# BlockController.net
KiCad netlist of a schematic drawn in EAGLE
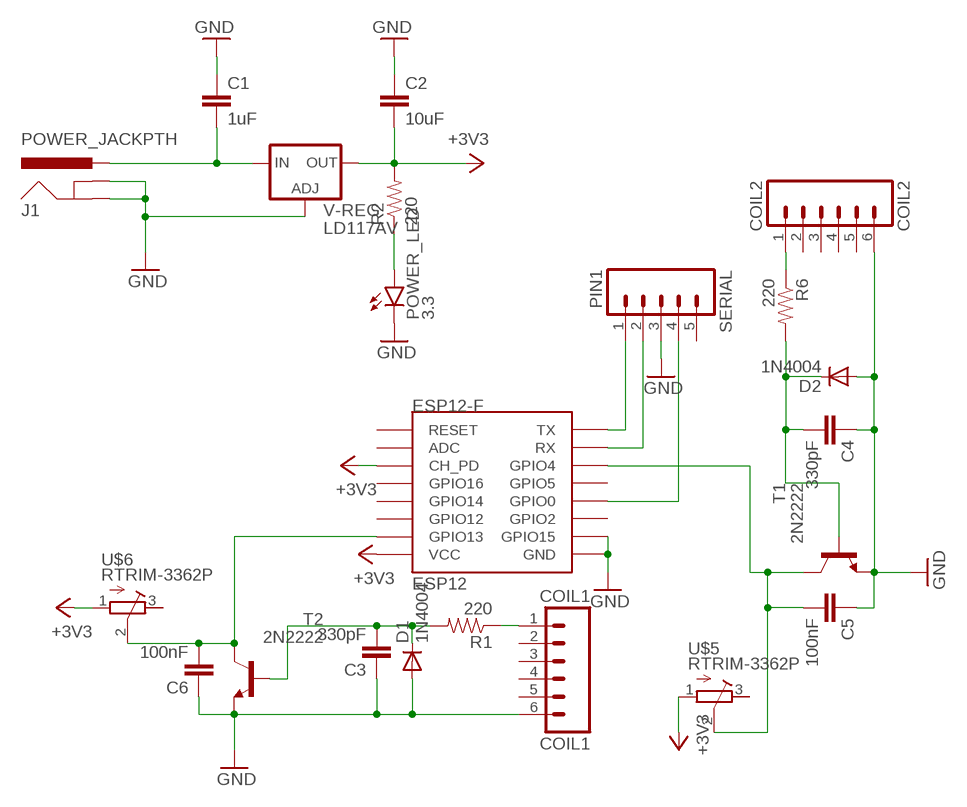
[diagram p0: schematic, sheet 1]

(export (version "E")
  (design (tool "Eeschema 10.0.6"))
  (components
    (comp (ref "C1")
      (value "1uF")
      (footprint "eagle-import:CAP-PTH-SMALL")
      (libsource (lib "eagle-import") (part "CAPPTH"))
    )
    (comp (ref "C2")
      (value "10uF")
      (footprint "eagle-import:CAP-PTH-SMALL")
      (libsource (lib "eagle-import") (part "CAPPTH"))
    )
    (comp (ref "C3")
      (value "330pF")
      (footprint "eagle-import:CAP-PTH-SMALL")
      (libsource (lib "eagle-import") (part "CAPPTH"))
    )
    (comp (ref "C4")
      (value "330pF")
      (footprint "eagle-import:CAP-PTH-SMALL")
      (libsource (lib "eagle-import") (part "CAPPTH"))
    )
    (comp (ref "C5")
      (value "100nF")
      (footprint "eagle-import:CAP-PTH-SMALL")
      (libsource (lib "eagle-import") (part "CAPPTH"))
    )
    (comp (ref "C6")
      (value "100nF")
      (footprint "eagle-import:CAP-PTH-SMALL")
      (libsource (lib "eagle-import") (part "CAPPTH"))
    )
    (comp (ref "COIL1")
      (value "COIL1")
      (footprint "eagle-import:06P")
      (libsource (lib "eagle-import") (part "M06"))
    )
    (comp (ref "COIL2")
      (value "COIL2")
      (footprint "eagle-import:06P")
      (libsource (lib "eagle-import") (part "M06"))
    )
    (comp (ref "D1")
      (value "1N4004")
      (footprint "eagle-import:DO41-10")
      (libsource (lib "eagle-import") (part "1N4004"))
    )
    (comp (ref "D2")
      (value "1N4004")
      (footprint "eagle-import:DO41-10")
      (libsource (lib "eagle-import") (part "1N4004"))
    )
    (comp (ref "ESP12-F")
      (value "ESP12")
      (footprint "eagle-import:ESP12")
      (libsource (lib "eagle-import") (part "ESP12"))
    )
    (comp (ref "J1")
      (value "POWER_JACKPTH")
      (footprint "eagle-import:POWER_JACK_PTH")
      (libsource (lib "eagle-import") (part "POWER_JACKPTH"))
    )
    (comp (ref "POWER_LED")
      (value "3.3")
      (footprint "eagle-import:LED5MM")
      (libsource (lib "eagle-import") (part "LED5MM"))
    )
    (comp (ref "R1")
      (value "220")
      (footprint "eagle-import:AXIAL-0.4")
      (libsource (lib "eagle-import") (part "RESISTORPTH-1/4W"))
    )
    (comp (ref "R2")
      (value "220")
      (footprint "eagle-import:AXIAL-0.4")
      (libsource (lib "eagle-import") (part "RESISTORPTH-1/4W"))
    )
    (comp (ref "R6")
      (value "220")
      (footprint "eagle-import:AXIAL-0.4")
      (libsource (lib "eagle-import") (part "RESISTORPTH-1/4W"))
    )
    (comp (ref "SERIAL")
      (value "PIN1")
      (footprint "eagle-import:05P")
      (libsource (lib "eagle-import") (part "M05"))
    )
    (comp (ref "T1")
      (value "2N2222")
      (footprint "eagle-import:TO18")
      (libsource (lib "eagle-import") (part "2N2222"))
    )
    (comp (ref "T2")
      (value "2N2222")
      (footprint "eagle-import:TO18")
      (libsource (lib "eagle-import") (part "2N2222"))
    )
    (comp (ref "U$5")
      (value "RTRIM-3362P")
      (footprint "eagle-import:RTRIM3362P")
      (libsource (lib "eagle-import") (part "RTRIM-3362P"))
    )
    (comp (ref "U$6")
      (value "RTRIM-3362P")
      (footprint "eagle-import:RTRIM3362P")
      (libsource (lib "eagle-import") (part "RTRIM-3362P"))
    )
    (comp (ref "V-REG")
      (value "LD117AV")
      (footprint "eagle-import:TO220L1")
      (libsource (lib "eagle-import") (part "LD117A?V"))
    )
  )
  (nets
    (net (code "1") (name "+3V3") (class "Default")
      (node (ref "C2") (pin "2") (pinfunction "2_2") (pintype "passive"))
      (node (ref "ESP12-F") (pin "CH_PD") (pinfunction "CH_PD_CH_PD") (pintype "bidirectional"))
      (node (ref "ESP12-F") (pin "VCC") (pinfunction "VCC_VCC") (pintype "bidirectional"))
      (node (ref "R2") (pin "P$2") (pinfunction "2_P$2") (pintype "passive"))
      (node (ref "U$5") (pin "1") (pinfunction "1_1") (pintype "passive"))
      (node (ref "U$6") (pin "1") (pinfunction "1_1") (pintype "passive"))
      (node (ref "V-REG") (pin "2") (pinfunction "OUT_2") (pintype "passive"))
    )
    (net (code "2") (name "GND") (class "Default")
      (node (ref "C1") (pin "1") (pinfunction "1_1") (pintype "passive"))
      (node (ref "C2") (pin "1") (pinfunction "1_1") (pintype "passive"))
      (node (ref "C3") (pin "1") (pinfunction "1_1") (pintype "passive"))
      (node (ref "C4") (pin "1") (pinfunction "1_1") (pintype "passive"))
      (node (ref "C5") (pin "1") (pinfunction "1_1") (pintype "passive"))
      (node (ref "C6") (pin "1") (pinfunction "1_1") (pintype "passive"))
      (node (ref "COIL1") (pin "6") (pinfunction "6_6") (pintype "passive"))
      (node (ref "COIL2") (pin "6") (pinfunction "6_6") (pintype "passive"))
      (node (ref "D1") (pin "A") (pinfunction "A_A") (pintype "passive"))
      (node (ref "D2") (pin "A") (pinfunction "A_A") (pintype "passive"))
      (node (ref "ESP12-F") (pin "GND") (pinfunction "GND_GND") (pintype "bidirectional"))
      (node (ref "ESP12-F") (pin "GPIO15") (pinfunction "GPIO15_GPIO15") (pintype "bidirectional"))
      (node (ref "J1") (pin "GND") (pinfunction "GND_GND") (pintype "bidirectional"))
      (node (ref "J1") (pin "GNDBREAK") (pinfunction "GNDBREAK_GNDBREAK") (pintype "bidirectional"))
      (node (ref "POWER_LED") (pin "K") (pinfunction "C_K") (pintype "passive"))
      (node (ref "SERIAL") (pin "3") (pinfunction "3_3") (pintype "passive"))
      (node (ref "T1") (pin "1") (pinfunction "E_1") (pintype "passive"))
      (node (ref "T2") (pin "1") (pinfunction "E_1") (pintype "passive"))
      (node (ref "V-REG") (pin "1") (pinfunction "ADJ_1") (pintype "input"))
    )
    (net (code "3") (name "Net-(ESP12-F-PadGPIO0)") (class "Default")
      (node (ref "ESP12-F") (pin "GPIO0") (pinfunction "GPIO0_GPIO0") (pintype "bidirectional"))
      (node (ref "SERIAL") (pin "4") (pinfunction "4_4") (pintype "passive"))
    )
    (net (code "4") (name "Net-(ESP12-F-PadRX)") (class "Default")
      (node (ref "ESP12-F") (pin "RX") (pinfunction "RX_RX") (pintype "bidirectional"))
      (node (ref "SERIAL") (pin "2") (pinfunction "2_2") (pintype "passive"))
    )
    (net (code "5") (name "Net-(ESP12-F-PadTX)") (class "Default")
      (node (ref "ESP12-F") (pin "TX") (pinfunction "TX_TX") (pintype "bidirectional"))
      (node (ref "SERIAL") (pin "1") (pinfunction "1_1") (pintype "passive"))
    )
    (net (code "6") (name "Net-(R1-1)") (class "Default")
      (node (ref "COIL1") (pin "1") (pinfunction "1_1") (pintype "passive"))
      (node (ref "R1") (pin "P$1") (pinfunction "1_P$1") (pintype "passive"))
    )
    (net (code "7") (name "Net-(R1-2)") (class "Default")
      (node (ref "C3") (pin "2") (pinfunction "2_2") (pintype "passive"))
      (node (ref "D1") (pin "C") (pinfunction "C_C") (pintype "passive"))
      (node (ref "R1") (pin "P$2") (pinfunction "2_P$2") (pintype "passive"))
      (node (ref "T2") (pin "2") (pinfunction "B_2") (pintype "passive"))
    )
    (net (code "8") (name "Net-(R2-1)") (class "Default")
      (node (ref "POWER_LED") (pin "A") (pinfunction "A_A") (pintype "passive"))
      (node (ref "R2") (pin "P$1") (pinfunction "1_P$1") (pintype "passive"))
    )
    (net (code "9") (name "Net-(R6-1)") (class "Default")
      (node (ref "COIL2") (pin "1") (pinfunction "1_1") (pintype "passive"))
      (node (ref "R6") (pin "P$1") (pinfunction "1_P$1") (pintype "passive"))
    )
    (net (code "10") (name "Net-(R6-2)") (class "Default")
      (node (ref "C4") (pin "2") (pinfunction "2_2") (pintype "passive"))
      (node (ref "D2") (pin "C") (pinfunction "C_C") (pintype "passive"))
      (node (ref "R6") (pin "P$2") (pinfunction "2_P$2") (pintype "passive"))
      (node (ref "T1") (pin "2") (pinfunction "B_2") (pintype "passive"))
    )
    (net (code "11") (name "Net-(T1-C)") (class "Default")
      (node (ref "C5") (pin "2") (pinfunction "2_2") (pintype "passive"))
      (node (ref "ESP12-F") (pin "GPIO4") (pinfunction "GPIO4_GPIO4") (pintype "bidirectional"))
      (node (ref "T1") (pin "3") (pinfunction "C_3") (pintype "passive"))
      (node (ref "U$5") (pin "2") (pinfunction "2_2") (pintype "passive"))
    )
    (net (code "12") (name "Net-(T2-C)") (class "Default")
      (node (ref "C6") (pin "2") (pinfunction "2_2") (pintype "passive"))
      (node (ref "ESP12-F") (pin "GPIO13") (pinfunction "GPIO13_GPIO13") (pintype "bidirectional"))
      (node (ref "T2") (pin "3") (pinfunction "C_3") (pintype "passive"))
      (node (ref "U$6") (pin "2") (pinfunction "2_2") (pintype "passive"))
    )
    (net (code "13") (name "Net-(V-REG-IN)") (class "Default")
      (node (ref "C1") (pin "2") (pinfunction "2_2") (pintype "passive"))
      (node (ref "J1") (pin "PWR") (pinfunction "PWR_PWR") (pintype "bidirectional"))
      (node (ref "V-REG") (pin "3") (pinfunction "IN_3") (pintype "input"))
    )
    (net (code "14") (name "unconnected-(COIL1-Pad2)") (class "Default")
      (node (ref "COIL1") (pin "2") (pinfunction "2_2") (pintype "passive"))
    )
    (net (code "15") (name "unconnected-(COIL1-Pad3)") (class "Default")
      (node (ref "COIL1") (pin "3") (pinfunction "3_3") (pintype "passive"))
    )
    (net (code "16") (name "unconnected-(COIL1-Pad4)") (class "Default")
      (node (ref "COIL1") (pin "4") (pinfunction "4_4") (pintype "passive"))
    )
    (net (code "17") (name "unconnected-(COIL1-Pad5)") (class "Default")
      (node (ref "COIL1") (pin "5") (pinfunction "5_5") (pintype "passive"))
    )
    (net (code "18") (name "unconnected-(COIL2-Pad2)") (class "Default")
      (node (ref "COIL2") (pin "2") (pinfunction "2_2") (pintype "passive"))
    )
    (net (code "19") (name "unconnected-(COIL2-Pad3)") (class "Default")
      (node (ref "COIL2") (pin "3") (pinfunction "3_3") (pintype "passive"))
    )
    (net (code "20") (name "unconnected-(COIL2-Pad4)") (class "Default")
      (node (ref "COIL2") (pin "4") (pinfunction "4_4") (pintype "passive"))
    )
    (net (code "21") (name "unconnected-(COIL2-Pad5)") (class "Default")
      (node (ref "COIL2") (pin "5") (pinfunction "5_5") (pintype "passive"))
    )
    (net (code "22") (name "unconnected-(ESP12-F-PadADC)") (class "Default")
      (node (ref "ESP12-F") (pin "ADC") (pinfunction "ADC_ADC") (pintype "bidirectional"))
    )
    (net (code "23") (name "unconnected-(ESP12-F-PadGPIO2)") (class "Default")
      (node (ref "ESP12-F") (pin "GPIO2") (pinfunction "GPIO2_GPIO2") (pintype "bidirectional"))
    )
    (net (code "24") (name "unconnected-(ESP12-F-PadGPIO5)") (class "Default")
      (node (ref "ESP12-F") (pin "GPIO5") (pinfunction "GPIO5_GPIO5") (pintype "bidirectional"))
    )
    (net (code "25") (name "unconnected-(ESP12-F-PadGPIO12)") (class "Default")
      (node (ref "ESP12-F") (pin "GPIO12") (pinfunction "GPIO12_GPIO12") (pintype "bidirectional"))
    )
    (net (code "26") (name "unconnected-(ESP12-F-PadGPIO14)") (class "Default")
      (node (ref "ESP12-F") (pin "GPIO14") (pinfunction "GPIO14_GPIO14") (pintype "bidirectional"))
    )
    (net (code "27") (name "unconnected-(ESP12-F-PadGPIO16)") (class "Default")
      (node (ref "ESP12-F") (pin "GPIO16") (pinfunction "GPIO16_GPIO16") (pintype "bidirectional"))
    )
    (net (code "28") (name "unconnected-(ESP12-F-PadRESET)") (class "Default")
      (node (ref "ESP12-F") (pin "RESET") (pinfunction "RESET_RESET") (pintype "bidirectional"))
    )
    (net (code "29") (name "unconnected-(SERIAL-Pad5)") (class "Default")
      (node (ref "SERIAL") (pin "5") (pinfunction "5_5") (pintype "passive"))
    )
    (net (code "30") (name "unconnected-(U$5-Pad3)") (class "Default")
      (node (ref "U$5") (pin "3") (pinfunction "3_3") (pintype "passive"))
    )
    (net (code "31") (name "unconnected-(U$6-Pad3)") (class "Default")
      (node (ref "U$6") (pin "3") (pinfunction "3_3") (pintype "passive"))
    )
  )
)
